# 3V3_LDO.net
KiCad netlist of a schematic drawn in Altium Designer
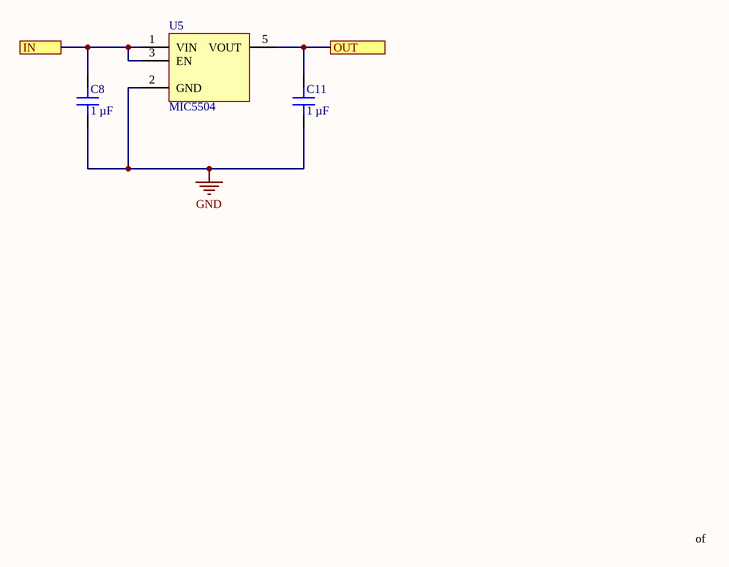
[diagram p0: 3V3_LDO.SchDoc]

(export (version "E")
  (design (tool "Eeschema 10.0.6"))
  (components
    (comp (ref "C8")
      (value "1 µF")
      (footprint "CAP 0402_1005")
      (description "CAP CER 0.1UF 16V X7R 0402")
      (fields (field (name "PART NUMBER") "C0402C104K4RACAUTO") (field (name "MANUFACTURER") "KEMET"))
      (libsource (lib "Celestial Altium Library - altium_library") (part "Capacitor"))
    )
    (comp (ref "C11")
      (value "1 µF")
      (footprint "CAP 0402_1005")
      (description "CAP CER 0.1UF 16V X7R 0402")
      (fields (field (name "PART NUMBER") "C0402C104K4RACAUTO") (field (name "MANUFACTURER") "KEMET"))
      (libsource (lib "Celestial Altium Library - altium_library") (part "Capacitor"))
    )
    (comp (ref "U5")
      (value "MIC5504")
      (footprint "TI SOT-23-5 DBV")
      (description "3.3V LDO")
      (libsource (lib "IC") (part "MIC5504-3.3YM5"))
    )
  )
  (nets
    (net (code "1") (name "/IN") (class "Default")
      (node (ref "C8") (pin "2") (pinfunction "2_2") (pintype "passive"))
      (node (ref "U5") (pin "1") (pinfunction "VIN_1") (pintype "passive"))
      (node (ref "U5") (pin "3") (pinfunction "EN_3") (pintype "passive"))
    )
    (net (code "2") (name "/OUT") (class "Default")
      (node (ref "C11") (pin "2") (pinfunction "2_2") (pintype "passive"))
      (node (ref "U5") (pin "5") (pinfunction "VOUT_5") (pintype "passive"))
    )
    (net (code "3") (name "GND") (class "Default")
      (node (ref "C11") (pin "1") (pinfunction "1_1") (pintype "passive"))
      (node (ref "C8") (pin "1") (pinfunction "1_1") (pintype "passive"))
      (node (ref "U5") (pin "2") (pinfunction "GND_2") (pintype "passive"))
    )
  )
)
